# IMU-BLIMP.net
KiCad netlist of a schematic drawn in EAGLE
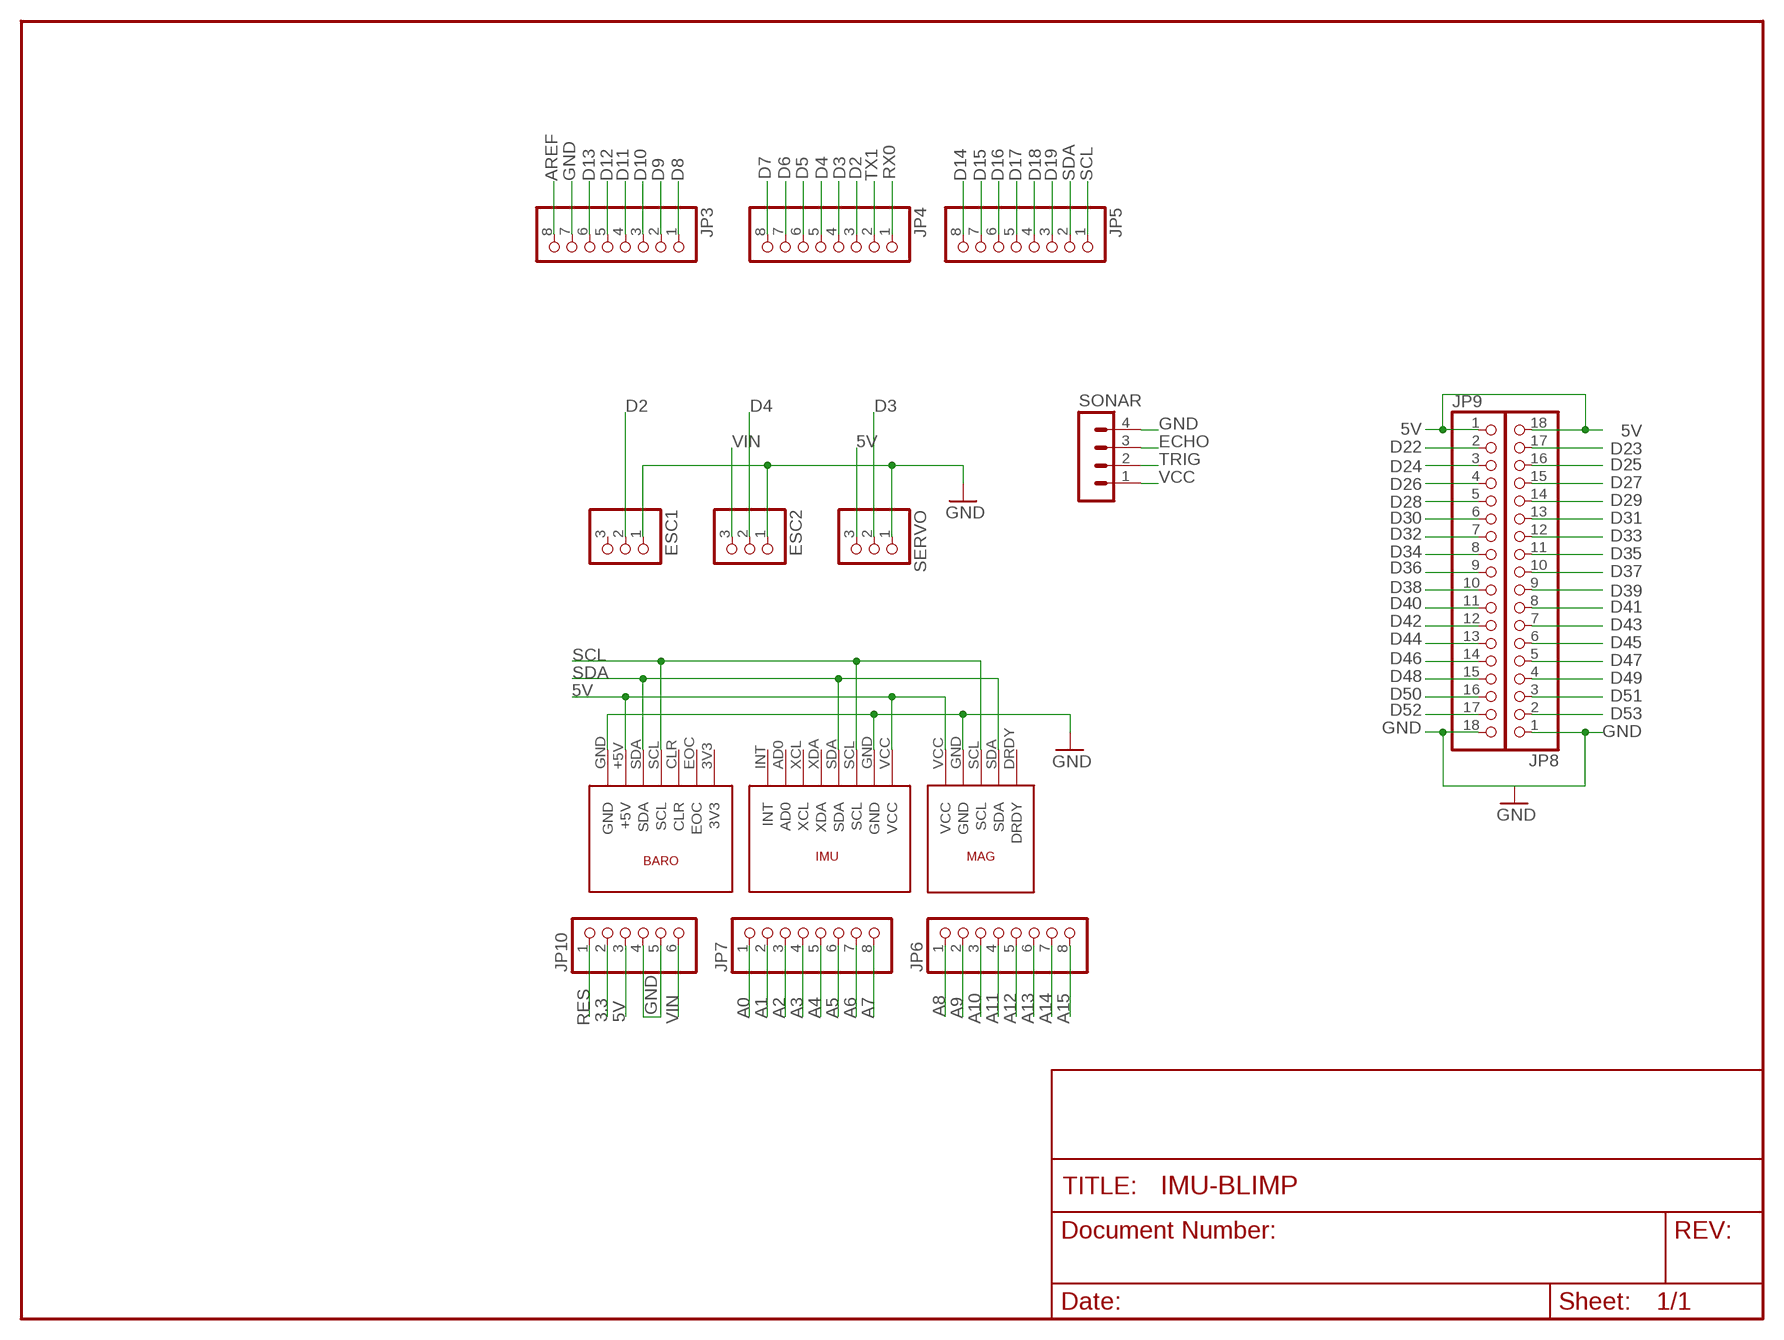
[diagram p0: schematic, sheet 1]

(export (version "E")
  (design (tool "Eeschema 10.0.6"))
  (components
    (comp (ref "BARO1")
      (value "BMP085")
      (footprint "eagle-import:BMP085")
      (libsource (lib "eagle-import") (part "BMP085"))
    )
    (comp (ref "ESC1")
      (value "PINHD-1X3CB")
      (footprint "eagle-import:1X03-CLEANBIG")
      (libsource (lib "eagle-import") (part "PINHD-1X3CB"))
    )
    (comp (ref "ESC2")
      (value "PINHD-1X3CB")
      (footprint "eagle-import:1X03-CLEANBIG")
      (libsource (lib "eagle-import") (part "PINHD-1X3CB"))
    )
    (comp (ref "IMU1")
      (value "MPU6050")
      (footprint "eagle-import:MPU6050")
      (libsource (lib "eagle-import") (part "MPU6050"))
    )
    (comp (ref "JP3")
      (value "PINHD-1X8CLEANBIG")
      (footprint "eagle-import:1X08-CLEANBIG")
      (libsource (lib "eagle-import") (part "PINHD-1X8CLEANBIG"))
    )
    (comp (ref "JP4")
      (value "PINHD-1X8CLEANBIG")
      (footprint "eagle-import:1X08-CLEANBIG")
      (libsource (lib "eagle-import") (part "PINHD-1X8CLEANBIG"))
    )
    (comp (ref "JP5")
      (value "PINHD-1X8CLEANBIG")
      (footprint "eagle-import:1X08-CLEANBIG")
      (libsource (lib "eagle-import") (part "PINHD-1X8CLEANBIG"))
    )
    (comp (ref "JP6")
      (value "PINHD-1X8CLEANBIG")
      (footprint "eagle-import:1X08-CLEANBIG")
      (libsource (lib "eagle-import") (part "PINHD-1X8CLEANBIG"))
    )
    (comp (ref "JP7")
      (value "PINHD-1X8CLEANBIG")
      (footprint "eagle-import:1X08-CLEANBIG")
      (libsource (lib "eagle-import") (part "PINHD-1X8CLEANBIG"))
    )
    (comp (ref "JP8")
      (value "PINHD-1X18-BIG")
      (footprint "eagle-import:1X18-BIG")
      (libsource (lib "eagle-import") (part "PINHD-1X18-BIG"))
    )
    (comp (ref "JP9")
      (value "PINHD-1X18-BIG")
      (footprint "eagle-import:1X18-BIG")
      (libsource (lib "eagle-import") (part "PINHD-1X18-BIG"))
    )
    (comp (ref "JP10")
      (value "PINHD-1X6CB")
      (footprint "eagle-import:1X06-CLEANBIG")
      (libsource (lib "eagle-import") (part "PINHD-1X6CB"))
    )
    (comp (ref "MAG1")
      (value "HMC5883L")
      (footprint "eagle-import:HMC5883L")
      (libsource (lib "eagle-import") (part "HMC5883L"))
    )
    (comp (ref "SERVO")
      (value "PINHD-1X3CB")
      (footprint "eagle-import:1X03-CLEANBIG")
      (libsource (lib "eagle-import") (part "PINHD-1X3CB"))
    )
    (comp (ref "SONAR")
      (value "MA04-1")
      (footprint "eagle-import:MA04-1")
      (libsource (lib "eagle-import") (part "MA04-1"))
    )
  )
  (nets
    (net (code "1") (name "/3.3") (class "Default")
      (node (ref "JP10") (pin "2") (pinfunction "2_2") (pintype "passive"))
    )
    (net (code "2") (name "/5V") (class "Default")
      (node (ref "BARO1") (pin "+5V") (pinfunction "+5V_+5V") (pintype "bidirectional"))
      (node (ref "IMU1") (pin "VCC") (pinfunction "VCC_VCC") (pintype "bidirectional"))
      (node (ref "JP10") (pin "3") (pinfunction "3_3") (pintype "passive"))
      (node (ref "JP8") (pin "18") (pinfunction "18_18") (pintype "passive"))
      (node (ref "JP9") (pin "1") (pinfunction "1_1") (pintype "passive"))
      (node (ref "MAG1") (pin "VCC") (pinfunction "VCC_VCC") (pintype "bidirectional"))
      (node (ref "SERVO") (pin "3") (pinfunction "3_3") (pintype "passive"))
      (node (ref "SONAR") (pin "1") (pinfunction "1_1") (pintype "passive"))
    )
    (net (code "3") (name "/A0") (class "Default")
      (node (ref "JP7") (pin "1") (pinfunction "1_1") (pintype "passive"))
    )
    (net (code "4") (name "/A1") (class "Default")
      (node (ref "JP7") (pin "2") (pinfunction "2_2") (pintype "passive"))
    )
    (net (code "5") (name "/A2") (class "Default")
      (node (ref "JP7") (pin "3") (pinfunction "3_3") (pintype "passive"))
    )
    (net (code "6") (name "/A3") (class "Default")
      (node (ref "JP7") (pin "4") (pinfunction "4_4") (pintype "passive"))
    )
    (net (code "7") (name "/A4") (class "Default")
      (node (ref "JP7") (pin "5") (pinfunction "5_5") (pintype "passive"))
    )
    (net (code "8") (name "/A5") (class "Default")
      (node (ref "JP7") (pin "6") (pinfunction "6_6") (pintype "passive"))
    )
    (net (code "9") (name "/A6") (class "Default")
      (node (ref "JP7") (pin "7") (pinfunction "7_7") (pintype "passive"))
    )
    (net (code "10") (name "/A7") (class "Default")
      (node (ref "JP7") (pin "8") (pinfunction "8_8") (pintype "passive"))
    )
    (net (code "11") (name "/A8") (class "Default")
      (node (ref "JP6") (pin "1") (pinfunction "1_1") (pintype "passive"))
    )
    (net (code "12") (name "/A9") (class "Default")
      (node (ref "JP6") (pin "2") (pinfunction "2_2") (pintype "passive"))
    )
    (net (code "13") (name "/A10") (class "Default")
      (node (ref "JP6") (pin "3") (pinfunction "3_3") (pintype "passive"))
    )
    (net (code "14") (name "/A11") (class "Default")
      (node (ref "JP6") (pin "4") (pinfunction "4_4") (pintype "passive"))
    )
    (net (code "15") (name "/A12") (class "Default")
      (node (ref "JP6") (pin "5") (pinfunction "5_5") (pintype "passive"))
    )
    (net (code "16") (name "/A13") (class "Default")
      (node (ref "JP6") (pin "6") (pinfunction "6_6") (pintype "passive"))
    )
    (net (code "17") (name "/A14") (class "Default")
      (node (ref "JP6") (pin "7") (pinfunction "7_7") (pintype "passive"))
    )
    (net (code "18") (name "/A15") (class "Default")
      (node (ref "JP6") (pin "8") (pinfunction "8_8") (pintype "passive"))
    )
    (net (code "19") (name "/AREF") (class "Default")
      (node (ref "JP3") (pin "8") (pinfunction "8_8") (pintype "passive"))
    )
    (net (code "20") (name "/D2") (class "Default")
      (node (ref "ESC1") (pin "2") (pinfunction "2_2") (pintype "passive"))
      (node (ref "JP4") (pin "3") (pinfunction "3_3") (pintype "passive"))
    )
    (net (code "21") (name "/D3") (class "Default")
      (node (ref "JP4") (pin "4") (pinfunction "4_4") (pintype "passive"))
      (node (ref "SERVO") (pin "2") (pinfunction "2_2") (pintype "passive"))
    )
    (net (code "22") (name "/D4") (class "Default")
      (node (ref "ESC2") (pin "2") (pinfunction "2_2") (pintype "passive"))
      (node (ref "JP4") (pin "5") (pinfunction "5_5") (pintype "passive"))
    )
    (net (code "23") (name "/D5") (class "Default")
      (node (ref "JP4") (pin "6") (pinfunction "6_6") (pintype "passive"))
      (node (ref "SONAR") (pin "3") (pinfunction "3_3") (pintype "passive"))
    )
    (net (code "24") (name "/D6") (class "Default")
      (node (ref "JP4") (pin "7") (pinfunction "7_7") (pintype "passive"))
      (node (ref "SONAR") (pin "2") (pinfunction "2_2") (pintype "passive"))
    )
    (net (code "25") (name "/D7") (class "Default")
      (node (ref "JP4") (pin "8") (pinfunction "8_8") (pintype "passive"))
    )
    (net (code "26") (name "/D8") (class "Default")
      (node (ref "JP3") (pin "1") (pinfunction "1_1") (pintype "passive"))
    )
    (net (code "27") (name "/D9") (class "Default")
      (node (ref "JP3") (pin "2") (pinfunction "2_2") (pintype "passive"))
    )
    (net (code "28") (name "/D10") (class "Default")
      (node (ref "JP3") (pin "3") (pinfunction "3_3") (pintype "passive"))
    )
    (net (code "29") (name "/D11") (class "Default")
      (node (ref "JP3") (pin "4") (pinfunction "4_4") (pintype "passive"))
    )
    (net (code "30") (name "/D12") (class "Default")
      (node (ref "JP3") (pin "5") (pinfunction "5_5") (pintype "passive"))
    )
    (net (code "31") (name "/D13") (class "Default")
      (node (ref "JP3") (pin "6") (pinfunction "6_6") (pintype "passive"))
    )
    (net (code "32") (name "/D14") (class "Default")
      (node (ref "JP5") (pin "8") (pinfunction "8_8") (pintype "passive"))
    )
    (net (code "33") (name "/D15") (class "Default")
      (node (ref "JP5") (pin "7") (pinfunction "7_7") (pintype "passive"))
    )
    (net (code "34") (name "/D16") (class "Default")
      (node (ref "JP5") (pin "6") (pinfunction "6_6") (pintype "passive"))
    )
    (net (code "35") (name "/D17") (class "Default")
      (node (ref "JP5") (pin "5") (pinfunction "5_5") (pintype "passive"))
    )
    (net (code "36") (name "/D18") (class "Default")
      (node (ref "JP5") (pin "4") (pinfunction "4_4") (pintype "passive"))
    )
    (net (code "37") (name "/D19") (class "Default")
      (node (ref "JP5") (pin "3") (pinfunction "3_3") (pintype "passive"))
    )
    (net (code "38") (name "/D22") (class "Default")
      (node (ref "JP9") (pin "2") (pinfunction "2_2") (pintype "passive"))
    )
    (net (code "39") (name "/D23") (class "Default")
      (node (ref "JP8") (pin "17") (pinfunction "17_17") (pintype "passive"))
    )
    (net (code "40") (name "/D24") (class "Default")
      (node (ref "JP9") (pin "3") (pinfunction "3_3") (pintype "passive"))
    )
    (net (code "41") (name "/D25") (class "Default")
      (node (ref "JP8") (pin "16") (pinfunction "16_16") (pintype "passive"))
    )
    (net (code "42") (name "/D26") (class "Default")
      (node (ref "JP9") (pin "4") (pinfunction "4_4") (pintype "passive"))
    )
    (net (code "43") (name "/D27") (class "Default")
      (node (ref "JP8") (pin "15") (pinfunction "15_15") (pintype "passive"))
    )
    (net (code "44") (name "/D28") (class "Default")
      (node (ref "JP9") (pin "5") (pinfunction "5_5") (pintype "passive"))
    )
    (net (code "45") (name "/D29") (class "Default")
      (node (ref "JP8") (pin "14") (pinfunction "14_14") (pintype "passive"))
    )
    (net (code "46") (name "/D30") (class "Default")
      (node (ref "JP9") (pin "6") (pinfunction "6_6") (pintype "passive"))
    )
    (net (code "47") (name "/D31") (class "Default")
      (node (ref "JP8") (pin "13") (pinfunction "13_13") (pintype "passive"))
    )
    (net (code "48") (name "/D32") (class "Default")
      (node (ref "JP9") (pin "7") (pinfunction "7_7") (pintype "passive"))
    )
    (net (code "49") (name "/D33") (class "Default")
      (node (ref "JP8") (pin "12") (pinfunction "12_12") (pintype "passive"))
    )
    (net (code "50") (name "/D34") (class "Default")
      (node (ref "JP9") (pin "8") (pinfunction "8_8") (pintype "passive"))
    )
    (net (code "51") (name "/D35") (class "Default")
      (node (ref "JP8") (pin "11") (pinfunction "11_11") (pintype "passive"))
    )
    (net (code "52") (name "/D36") (class "Default")
      (node (ref "JP9") (pin "9") (pinfunction "9_9") (pintype "passive"))
    )
    (net (code "53") (name "/D37") (class "Default")
      (node (ref "JP8") (pin "10") (pinfunction "10_10") (pintype "passive"))
    )
    (net (code "54") (name "/D38") (class "Default")
      (node (ref "JP9") (pin "10") (pinfunction "10_10") (pintype "passive"))
    )
    (net (code "55") (name "/D39") (class "Default")
      (node (ref "JP8") (pin "9") (pinfunction "9_9") (pintype "passive"))
    )
    (net (code "56") (name "/D40") (class "Default")
      (node (ref "JP9") (pin "11") (pinfunction "11_11") (pintype "passive"))
    )
    (net (code "57") (name "/D41") (class "Default")
      (node (ref "JP8") (pin "8") (pinfunction "8_8") (pintype "passive"))
    )
    (net (code "58") (name "/D42") (class "Default")
      (node (ref "JP9") (pin "12") (pinfunction "12_12") (pintype "passive"))
    )
    (net (code "59") (name "/D43") (class "Default")
      (node (ref "JP8") (pin "7") (pinfunction "7_7") (pintype "passive"))
    )
    (net (code "60") (name "/D44") (class "Default")
      (node (ref "JP9") (pin "13") (pinfunction "13_13") (pintype "passive"))
    )
    (net (code "61") (name "/D45") (class "Default")
      (node (ref "JP8") (pin "6") (pinfunction "6_6") (pintype "passive"))
    )
    (net (code "62") (name "/D46") (class "Default")
      (node (ref "JP9") (pin "14") (pinfunction "14_14") (pintype "passive"))
    )
    (net (code "63") (name "/D47") (class "Default")
      (node (ref "JP8") (pin "5") (pinfunction "5_5") (pintype "passive"))
    )
    (net (code "64") (name "/D48") (class "Default")
      (node (ref "JP9") (pin "15") (pinfunction "15_15") (pintype "passive"))
    )
    (net (code "65") (name "/D49") (class "Default")
      (node (ref "JP8") (pin "4") (pinfunction "4_4") (pintype "passive"))
    )
    (net (code "66") (name "/D50") (class "Default")
      (node (ref "JP9") (pin "16") (pinfunction "16_16") (pintype "passive"))
    )
    (net (code "67") (name "/D51") (class "Default")
      (node (ref "JP8") (pin "3") (pinfunction "3_3") (pintype "passive"))
    )
    (net (code "68") (name "/D52") (class "Default")
      (node (ref "JP9") (pin "17") (pinfunction "17_17") (pintype "passive"))
    )
    (net (code "69") (name "/D53") (class "Default")
      (node (ref "JP8") (pin "2") (pinfunction "2_2") (pintype "passive"))
    )
    (net (code "70") (name "/RES") (class "Default")
      (node (ref "JP10") (pin "1") (pinfunction "1_1") (pintype "passive"))
    )
    (net (code "71") (name "/RX0") (class "Default")
      (node (ref "JP4") (pin "1") (pinfunction "1_1") (pintype "passive"))
    )
    (net (code "72") (name "/SCL") (class "Default")
      (node (ref "BARO1") (pin "SCL") (pinfunction "SCL_SCL") (pintype "bidirectional"))
      (node (ref "IMU1") (pin "SCL") (pinfunction "SCL_SCL") (pintype "bidirectional"))
      (node (ref "JP5") (pin "1") (pinfunction "1_1") (pintype "passive"))
      (node (ref "MAG1") (pin "SCL") (pinfunction "SCL_SCL") (pintype "bidirectional"))
    )
    (net (code "73") (name "/SDA") (class "Default")
      (node (ref "BARO1") (pin "SDA") (pinfunction "SDA_SDA") (pintype "bidirectional"))
      (node (ref "IMU1") (pin "SDA") (pinfunction "SDA_SDA") (pintype "bidirectional"))
      (node (ref "JP5") (pin "2") (pinfunction "2_2") (pintype "passive"))
      (node (ref "MAG1") (pin "SDA") (pinfunction "SDA_SDA") (pintype "bidirectional"))
    )
    (net (code "74") (name "/TX1") (class "Default")
      (node (ref "JP4") (pin "2") (pinfunction "2_2") (pintype "passive"))
    )
    (net (code "75") (name "/VIN") (class "Default")
      (node (ref "ESC2") (pin "3") (pinfunction "3_3") (pintype "passive"))
      (node (ref "JP10") (pin "6") (pinfunction "6_6") (pintype "passive"))
    )
    (net (code "76") (name "GND") (class "Default")
      (node (ref "BARO1") (pin "GND") (pinfunction "GND_GND") (pintype "bidirectional"))
      (node (ref "ESC1") (pin "1") (pinfunction "1_1") (pintype "passive"))
      (node (ref "ESC2") (pin "1") (pinfunction "1_1") (pintype "passive"))
      (node (ref "IMU1") (pin "GND") (pinfunction "GND_GND") (pintype "bidirectional"))
      (node (ref "JP10") (pin "4") (pinfunction "4_4") (pintype "passive"))
      (node (ref "JP10") (pin "5") (pinfunction "5_5") (pintype "passive"))
      (node (ref "JP3") (pin "7") (pinfunction "7_7") (pintype "passive"))
      (node (ref "JP8") (pin "1") (pinfunction "1_1") (pintype "passive"))
      (node (ref "JP9") (pin "18") (pinfunction "18_18") (pintype "passive"))
      (node (ref "MAG1") (pin "GND") (pinfunction "GND_GND") (pintype "bidirectional"))
      (node (ref "SERVO") (pin "1") (pinfunction "1_1") (pintype "passive"))
      (node (ref "SONAR") (pin "4") (pinfunction "4_4") (pintype "passive"))
    )
    (net (code "77") (name "unconnected-(BARO1-Pad3V3)") (class "Default")
      (node (ref "BARO1") (pin "3V3") (pinfunction "3V3_3V3") (pintype "bidirectional"))
    )
    (net (code "78") (name "unconnected-(BARO1-PadCLR)") (class "Default")
      (node (ref "BARO1") (pin "CLR") (pinfunction "CLR_CLR") (pintype "bidirectional"))
    )
    (net (code "79") (name "unconnected-(BARO1-PadEOC)") (class "Default")
      (node (ref "BARO1") (pin "EOC") (pinfunction "EOC_EOC") (pintype "bidirectional"))
    )
    (net (code "80") (name "unconnected-(ESC1-Pad3)") (class "Default")
      (node (ref "ESC1") (pin "3") (pinfunction "3_3") (pintype "passive"))
    )
    (net (code "81") (name "unconnected-(IMU1-PadAD0)") (class "Default")
      (node (ref "IMU1") (pin "AD0") (pinfunction "AD0_AD0") (pintype "bidirectional"))
    )
    (net (code "82") (name "unconnected-(IMU1-PadINT)") (class "Default")
      (node (ref "IMU1") (pin "INT") (pinfunction "INT_INT") (pintype "bidirectional"))
    )
    (net (code "83") (name "unconnected-(IMU1-PadXCL)") (class "Default")
      (node (ref "IMU1") (pin "XCL") (pinfunction "XCL_XCL") (pintype "bidirectional"))
    )
    (net (code "84") (name "unconnected-(IMU1-PadXDA)") (class "Default")
      (node (ref "IMU1") (pin "XDA") (pinfunction "XDA_XDA") (pintype "bidirectional"))
    )
    (net (code "85") (name "unconnected-(MAG1-PadDRDY)") (class "Default")
      (node (ref "MAG1") (pin "DRDY") (pinfunction "DRDY_DRDY") (pintype "bidirectional"))
    )
  )
)
